# 1.net
KiCad netlist of a schematic drawn in Altium Designer
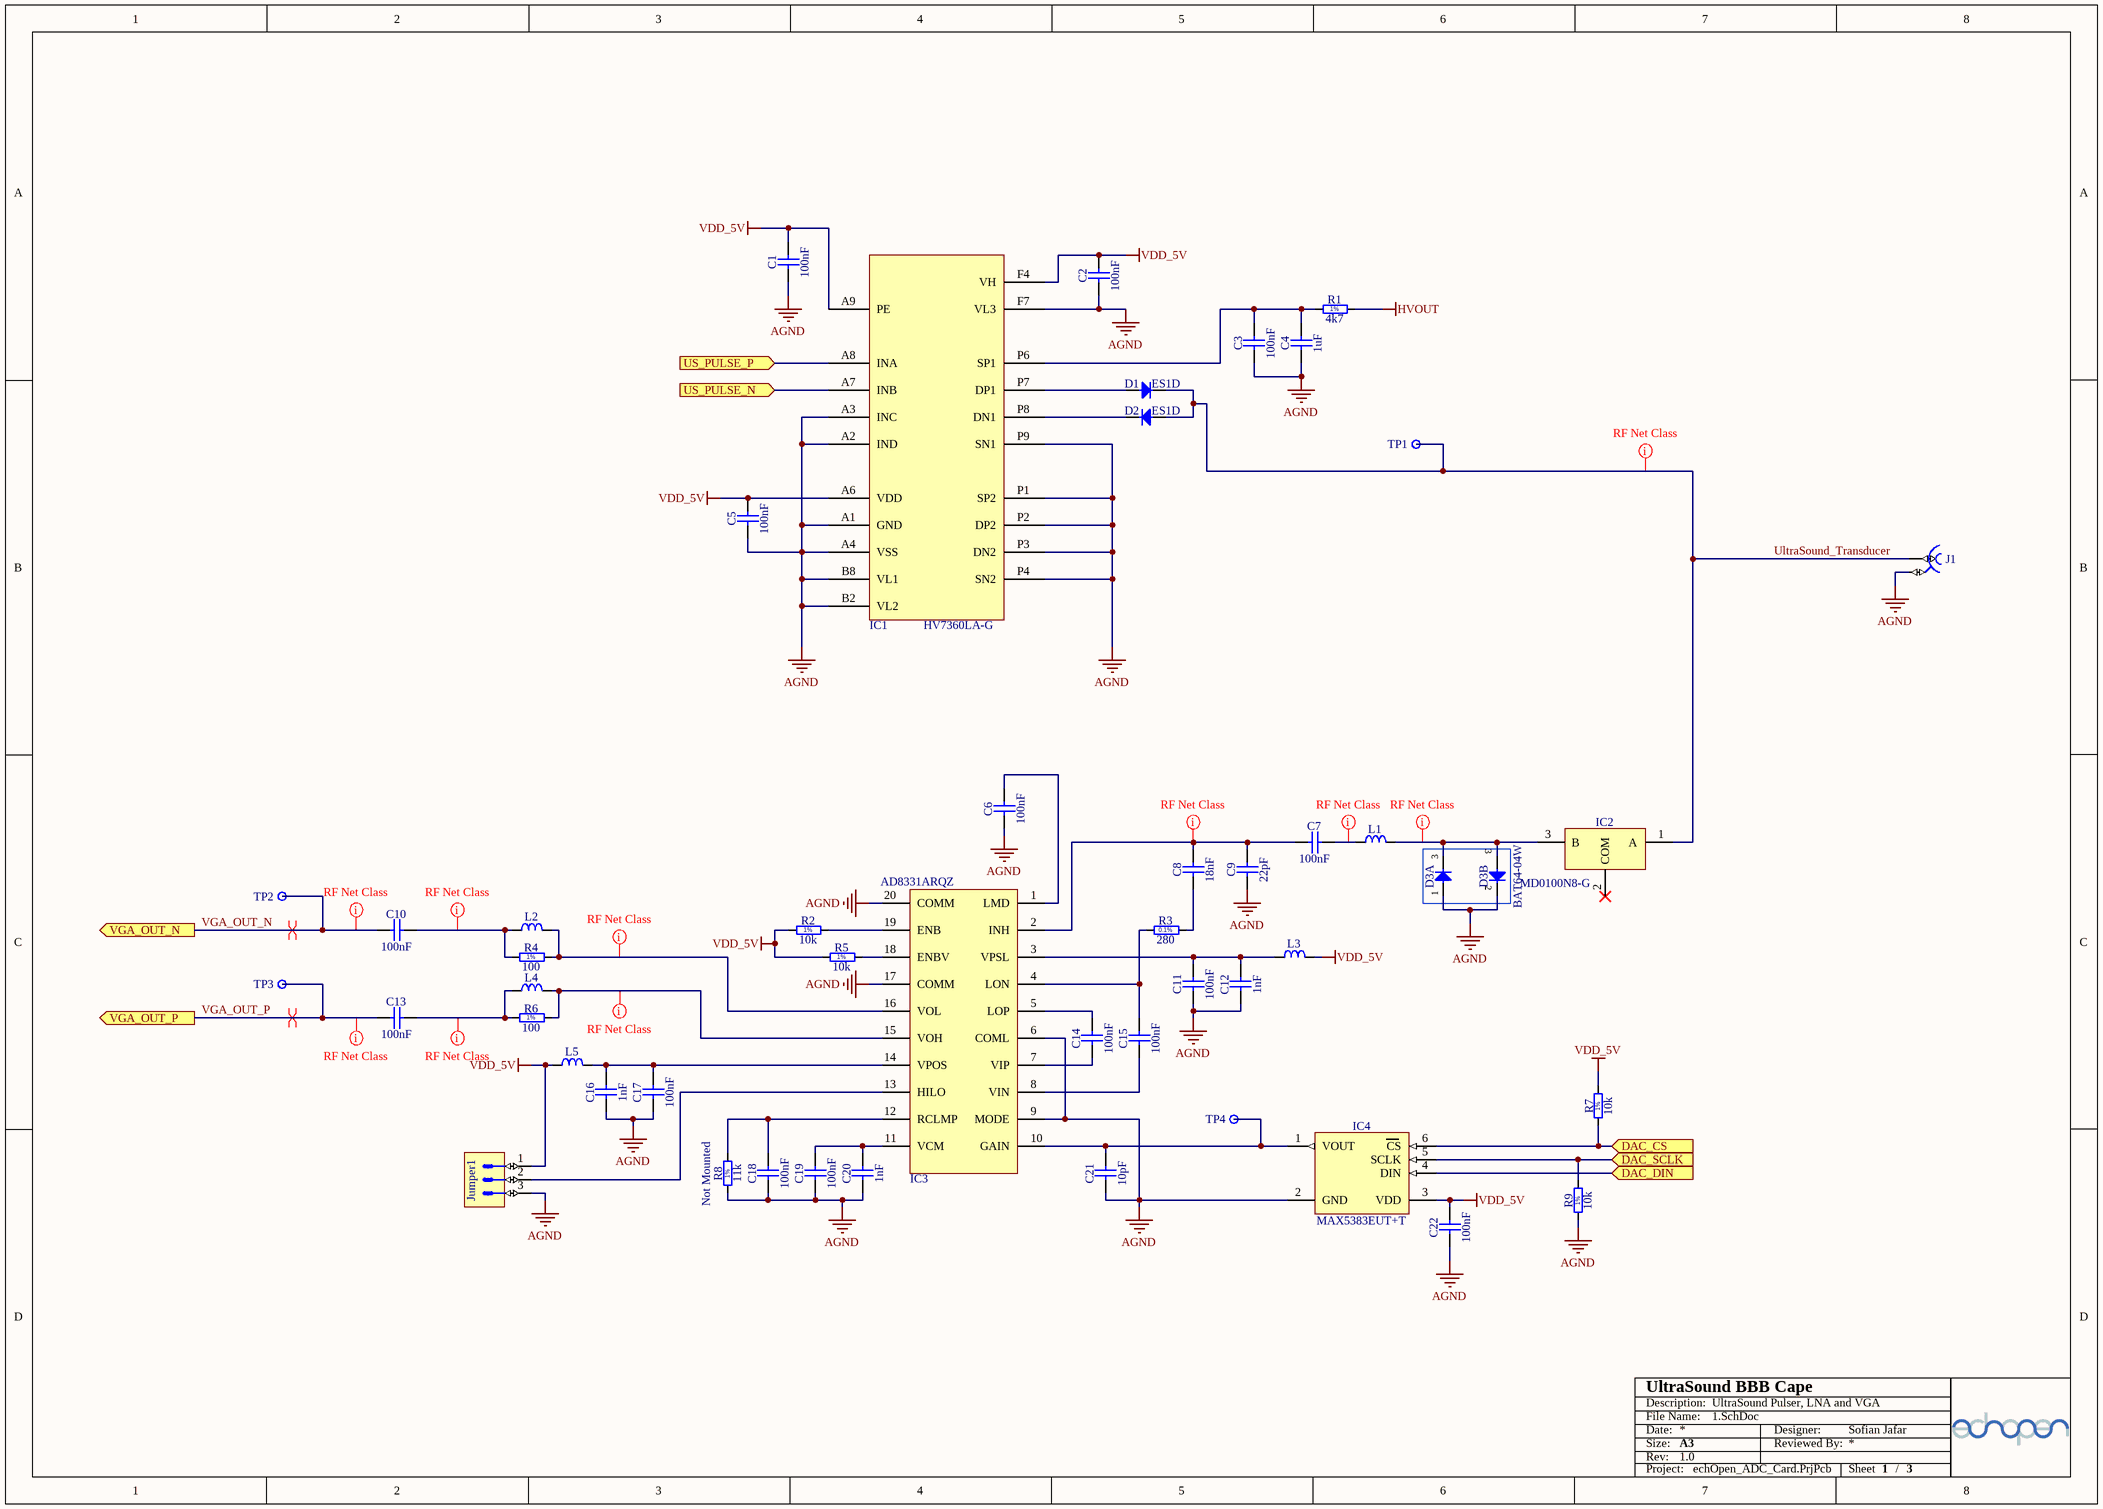
[diagram p0: 1.SchDoc]

(export (version "E")
  (design (tool "Eeschema 10.0.6"))
  (components
    (comp (ref "C1")
      (value "100nF")
      (footprint "CAPC1608X87N")
      (description "Non-polarised capacitor")
      (fields
        (field (name "PART NUMBER") "CC0603_100NF_50V_10%_X7R")
        (field (name "VOLTAGE") "50V")
        (field (name "AUTHOR") "CERN DEM JLC")
      )
      (libsource (lib "Sof-Capacitors") (part "Capacitor - non polarized"))
    )
    (comp (ref "C2")
      (value "100nF")
      (footprint "CAPC1608X87N")
      (description "Non-polarised capacitor")
      (fields
        (field (name "PART NUMBER") "CC0603_100NF_50V_10%_X7R")
        (field (name "VOLTAGE") "50V")
        (field (name "AUTHOR") "CERN DEM JLC")
      )
      (libsource (lib "Sof-Capacitors") (part "Capacitor - non polarized"))
    )
    (comp (ref "C3")
      (value "100nF")
      (footprint "CAPC1608X87N")
      (description "Non-polarised capacitor")
      (fields
        (field (name "PART NUMBER") "CC0603_100NF_50V_10%_X7R")
        (field (name "VOLTAGE") "50V")
        (field (name "AUTHOR") "CERN DEM JLC")
      )
      (libsource (lib "Sof-Capacitors") (part "Capacitor - non polarized"))
    )
    (comp (ref "C4")
      (value "1uF")
      (footprint "CAPC5650X165N")
      (description "Non-polarised capacitor")
      (fields
        (field (name "PART NUMBER") "CC2220_1UF_200V_10%_X7R")
        (field (name "VOLTAGE") "200V")
        (field (name "AUTHOR") "CERN DEM JLC")
      )
      (libsource (lib "Sof-Capacitors") (part "Capacitor - non polarized"))
    )
    (comp (ref "C5")
      (value "100nF")
      (footprint "CAPC1608X87N")
      (description "Non-polarised capacitor")
      (fields
        (field (name "PART NUMBER") "CC0603_100NF_50V_10%_X7R")
        (field (name "VOLTAGE") "50V")
        (field (name "AUTHOR") "CERN DEM JLC")
      )
      (libsource (lib "Sof-Capacitors") (part "Capacitor - non polarized"))
    )
    (comp (ref "C6")
      (value "100nF")
      (footprint "CAPC1608X87N")
      (description "Non-polarised capacitor")
      (fields
        (field (name "PART NUMBER") "CC0603_100NF_50V_10%_X7R")
        (field (name "VOLTAGE") "50V")
        (field (name "AUTHOR") "CERN DEM JLC")
      )
      (libsource (lib "Sof-Capacitors") (part "Capacitor - non polarized"))
    )
    (comp (ref "C7")
      (value "100nF")
      (footprint "CAPC1608X87N")
      (description "Non-polarised capacitor")
      (fields
        (field (name "PART NUMBER") "CC0603_100NF_50V_10%_X7R")
        (field (name "VOLTAGE") "50V")
        (field (name "AUTHOR") "CERN DEM JLC")
      )
      (libsource (lib "Sof-Capacitors") (part "Capacitor - non polarized"))
    )
    (comp (ref "C8")
      (value "18nF")
      (footprint "CAPC1608X87N")
      (description "Non-polarised capacitor")
      (fields
        (field (name "PART NUMBER") "CC0603_18NF_50V_10%_X7R")
        (field (name "VOLTAGE") "50V")
        (field (name "AUTHOR") "CERN DEM JLC")
      )
      (libsource (lib "Sof-Capacitors") (part "Capacitor - non polarized"))
    )
    (comp (ref "C9")
      (value "22pF")
      (footprint "CAPC1608X87N")
      (description "Non-polarised capacitor")
      (fields
        (field (name "PART NUMBER") "CC0603_22PF_50V_5%_NP0")
        (field (name "VOLTAGE") "50V")
        (field (name "AUTHOR") "CERN DEM JLC")
      )
      (libsource (lib "Sof-Capacitors") (part "Capacitor - non polarized"))
    )
    (comp (ref "C10")
      (value "100nF")
      (footprint "CAPC1608X87N")
      (description "Non-polarised capacitor")
      (fields
        (field (name "PART NUMBER") "CC0603_100NF_50V_10%_X7R")
        (field (name "VOLTAGE") "50V")
        (field (name "AUTHOR") "CERN DEM JLC")
      )
      (libsource (lib "Sof-Capacitors") (part "Capacitor - non polarized"))
    )
    (comp (ref "C11")
      (value "100nF")
      (footprint "CAPC1608X87N")
      (description "Non-polarised capacitor")
      (fields
        (field (name "PART NUMBER") "CC0603_100NF_50V_10%_X7R")
        (field (name "VOLTAGE") "50V")
        (field (name "AUTHOR") "CERN DEM JLC")
      )
      (libsource (lib "Sof-Capacitors") (part "Capacitor - non polarized"))
    )
    (comp (ref "C12")
      (value "1nF")
      (footprint "CAPC1608X87N")
      (description "Non-polarised capacitor")
      (fields
        (field (name "PART NUMBER") "CC0603_1NF_50V_10%_X7R")
        (field (name "VOLTAGE") "50V")
        (field (name "AUTHOR") "CERN DEM JLC")
      )
      (libsource (lib "Sof-Capacitors") (part "Capacitor - non polarized"))
    )
    (comp (ref "C13")
      (value "100nF")
      (footprint "CAPC1608X87N")
      (description "Non-polarised capacitor")
      (fields
        (field (name "PART NUMBER") "CC0603_100NF_50V_10%_X7R")
        (field (name "VOLTAGE") "50V")
        (field (name "AUTHOR") "CERN DEM JLC")
      )
      (libsource (lib "Sof-Capacitors") (part "Capacitor - non polarized"))
    )
    (comp (ref "C14")
      (value "100nF")
      (footprint "CAPC1608X87N")
      (description "Non-polarised capacitor")
      (fields
        (field (name "PART NUMBER") "CC0603_100NF_50V_10%_X7R")
        (field (name "VOLTAGE") "50V")
        (field (name "AUTHOR") "CERN DEM JLC")
      )
      (libsource (lib "Sof-Capacitors") (part "Capacitor - non polarized"))
    )
    (comp (ref "C15")
      (value "100nF")
      (footprint "CAPC1608X87N")
      (description "Non-polarised capacitor")
      (fields
        (field (name "PART NUMBER") "CC0603_100NF_50V_10%_X7R")
        (field (name "VOLTAGE") "50V")
        (field (name "AUTHOR") "CERN DEM JLC")
      )
      (libsource (lib "Sof-Capacitors") (part "Capacitor - non polarized"))
    )
    (comp (ref "C16")
      (value "1nF")
      (footprint "CAPC1608X87N")
      (description "Non-polarised capacitor")
      (fields
        (field (name "PART NUMBER") "CC0603_1NF_50V_10%_X7R")
        (field (name "VOLTAGE") "50V")
        (field (name "AUTHOR") "CERN DEM JLC")
      )
      (libsource (lib "Sof-Capacitors") (part "Capacitor - non polarized"))
    )
    (comp (ref "C17")
      (value "100nF")
      (footprint "CAPC1608X87N")
      (description "Non-polarised capacitor")
      (fields
        (field (name "PART NUMBER") "CC0603_100NF_50V_10%_X7R")
        (field (name "VOLTAGE") "50V")
        (field (name "AUTHOR") "CERN DEM JLC")
      )
      (libsource (lib "Sof-Capacitors") (part "Capacitor - non polarized"))
    )
    (comp (ref "C18")
      (value "100nF")
      (footprint "CAPC1608X87N")
      (description "Non-polarised capacitor")
      (fields
        (field (name "PART NUMBER") "CC0603_100NF_50V_10%_X7R")
        (field (name "VOLTAGE") "50V")
        (field (name "AUTHOR") "CERN DEM JLC")
      )
      (libsource (lib "Sof-Capacitors") (part "Capacitor - non polarized"))
    )
    (comp (ref "C19")
      (value "100nF")
      (footprint "CAPC1608X87N")
      (description "Non-polarised capacitor")
      (fields
        (field (name "PART NUMBER") "CC0603_100NF_50V_10%_X7R")
        (field (name "VOLTAGE") "50V")
        (field (name "AUTHOR") "CERN DEM JLC")
      )
      (libsource (lib "Sof-Capacitors") (part "Capacitor - non polarized"))
    )
    (comp (ref "C20")
      (value "1nF")
      (footprint "CAPC1608X87N")
      (description "Non-polarised capacitor")
      (fields
        (field (name "PART NUMBER") "CC0603_1NF_50V_10%_X7R")
        (field (name "VOLTAGE") "50V")
        (field (name "AUTHOR") "CERN DEM JLC")
      )
      (libsource (lib "Sof-Capacitors") (part "Capacitor - non polarized"))
    )
    (comp (ref "C21")
      (value "10pF")
      (footprint "CAPC1608X87N")
      (description "Non-polarised capacitor")
      (fields
        (field (name "PART NUMBER") "CC0603_10PF_50V_5%_NP0")
        (field (name "VOLTAGE") "50V")
        (field (name "AUTHOR") "CERN DEM JLC")
      )
      (libsource (lib "Sof-Capacitors") (part "Capacitor - non polarized"))
    )
    (comp (ref "C22")
      (value "100nF")
      (footprint "CAPC1608X87N")
      (description "Non-polarised capacitor")
      (fields
        (field (name "PART NUMBER") "CC0603_100NF_50V_10%_X7R")
        (field (name "VOLTAGE") "50V")
        (field (name "AUTHOR") "CERN DEM JLC")
      )
      (libsource (lib "Sof-Capacitors") (part "Capacitor - non polarized"))
    )
    (comp (ref "D1")
      (value "ES1D")
      (footprint "DIOM5027X244N")
      (description "Diode")
      (fields
        (field (name "VOLTAGE") "200V")
        (field (name "POWER") "1A")
        (field (name "AUTHOR") "CERN DEM JLC")
      )
      (libsource (lib "Sof-ICs And Semiconductors") (part "Diode"))
    )
    (comp (ref "D2")
      (value "ES1D")
      (footprint "DIOM5027X244N")
      (description "Diode")
      (fields
        (field (name "VOLTAGE") "200V")
        (field (name "POWER") "1A")
        (field (name "AUTHOR") "CERN DEM JLC")
      )
      (libsource (lib "Sof-ICs And Semiconductors") (part "Diode"))
    )
    (comp (ref "D3")
      (value "BAT64-04W")
      (footprint "SOT65P210X100-3N")
      (description "Serial Diode")
      (fields
        (field (name "VOLTAGE") "40V")
        (field (name "POWER") "250mW")
        (field (name "AUTHOR") "CERN DEM JMW")
      )
      (libsource (lib "Sof-ICs And Semiconductors") (part "Diode x2 A1C3_A3C2"))
    )
    (comp (ref "IC1")
      (value "HV7360LA-G")
      (footprint "HV7360")
      (fields (field (name "MANUFACTURER") "Supertex inc.") (field (name "AUTHOR") "S. Jafar"))
      (libsource (lib "Sof-ICs And Semiconductors") (part "HV7360"))
    )
    (comp (ref "IC2")
      (value "MD0100N8-G")
      (footprint "SOT89")
      (description "3-Ultra-Sound HV Switch 1=A 2=COM 3=B")
      (fields (field (name "MANUFACTURER") "Supertex inc.") (field (name "AUTHOR") "S. Jafar"))
      (libsource (lib "Sof-ICs And Semiconductors") (part "MD0100"))
    )
    (comp (ref "IC3")
      (value "AD8331ARQZ")
      (footprint "SOP64P600X175-20N")
      (fields (field (name "MANUFACTURER") "Analog Devices") (field (name "AUTHOR") "S. Jafar"))
      (libsource (lib "Sof-ICs And Semiconductors") (part "AD8331"))
    )
    (comp (ref "IC4")
      (value "MAX5383EUT+T")
      (footprint "SOT95P280X100-6N")
      (description "Low-Cost, Low-Power, 8-Bit DACs with 3-Wire  Serial Interface in SOT23")
      (fields (field (name "MANUFACTURER") "MAXIM") (field (name "AUTHOR") "S. Jafar"))
      (libsource (lib "Sof-ICs And Semiconductors") (part "MAX5383"))
    )
    (comp (ref "J1")
      (value "SMA")
      (footprint "AMPHENOL_132357-11")
      (fields
        (field (name "PART NUMBER") "AMPHENOL_132357-11")
        (field (name "MANUFACTURER") "AMPHENOL")
        (field (name "MANUFACTURER PART NUMBER") "132357-11")
        (field (name "AUTHOR") "CERN DEM JLC")
      )
      (libsource (lib "Sof-Connectors") (part "Coax_1Female_1Shield"))
    )
    (comp (ref "Jumper1")
      (value "~")
      (footprint "SULLINS_GRPB031VWVN")
      (description "Connector 3 Male")
      (fields
        (field (name "PART NUMBER") "SULLINS_GRPB031VWVN")
        (field (name "MANUFACTURER") "SULLINS")
        (field (name "AUTHOR") "S. Jafar")
      )
      (libsource (lib "Sof-Connectors") (part "Connector 3 Male"))
    )
    (comp (ref "L1")
      (value "75R@100MHz")
      (footprint "INDC2012X105N")
      (description "Inductor")
      (fields
        (field (name "PART NUMBER") "IND0805_MURATA_BLM21BB750SN1D")
        (field (name "POWER") "700mA")
        (field (name "AUTHOR") "S. Jafar")
      )
      (libsource (lib "Sof-Inductors & Transformers") (part "Inductor"))
    )
    (comp (ref "L2")
      (value "75R@100MHz")
      (footprint "INDC2012X105N")
      (description "Inductor")
      (fields
        (field (name "PART NUMBER") "IND0805_MURATA_BLM21BB750SN1D")
        (field (name "POWER") "700mA")
        (field (name "AUTHOR") "S. Jafar")
      )
      (libsource (lib "Sof-Inductors & Transformers") (part "Inductor"))
    )
    (comp (ref "L3")
      (value "75R@100MHz")
      (footprint "INDC2012X105N")
      (description "Inductor")
      (fields
        (field (name "PART NUMBER") "IND0805_MURATA_BLM21BB750SN1D")
        (field (name "POWER") "700mA")
        (field (name "AUTHOR") "S. Jafar")
      )
      (libsource (lib "Sof-Inductors & Transformers") (part "Inductor"))
    )
    (comp (ref "L4")
      (value "75R@100MHz")
      (footprint "INDC2012X105N")
      (description "Inductor")
      (fields
        (field (name "PART NUMBER") "IND0805_MURATA_BLM21BB750SN1D")
        (field (name "POWER") "700mA")
        (field (name "AUTHOR") "S. Jafar")
      )
      (libsource (lib "Sof-Inductors & Transformers") (part "Inductor"))
    )
    (comp (ref "L5")
      (value "75R@100MHz")
      (footprint "INDC2012X105N")
      (description "Inductor")
      (fields
        (field (name "PART NUMBER") "IND0805_MURATA_BLM21BB750SN1D")
        (field (name "POWER") "700mA")
        (field (name "AUTHOR") "S. Jafar")
      )
      (libsource (lib "Sof-Inductors & Transformers") (part "Inductor"))
    )
    (comp (ref "R1")
      (value "4k7")
      (footprint "RESC3216X65N")
      (description "Resistor - 1%")
      (fields
        (field (name "PART NUMBER") "R1206_4K7_1%_0.25W_100PPM")
        (field (name "POWER") "0.25W")
        (field (name "AUTHOR") "CERN DEM JLC")
      )
      (libsource (lib "Sof-Resistors") (part "Resistor - 1%"))
    )
    (comp (ref "R2")
      (value "10k")
      (footprint "RESC1608X55N")
      (description "Resistor - 1%")
      (fields
        (field (name "PART NUMBER") "R0603_10K_1%_0.1W_100PPM")
        (field (name "POWER") "0.1W")
        (field (name "AUTHOR") "CERN DEM JLC")
      )
      (libsource (lib "Sof-Resistors") (part "Resistor - 1%"))
    )
    (comp (ref "R3")
      (value "280")
      (footprint "RESC1608X55N")
      (description "Resistor - 0.1%")
      (fields
        (field (name "PART NUMBER") "R0603_280R_0.1%_0.063W_10PPM")
        (field (name "POWER") "0.063W")
        (field (name "AUTHOR") "CERN DEM JLC")
      )
      (libsource (lib "Sof-Resistors") (part "Resistor - 0.1%"))
    )
    (comp (ref "R4")
      (value "100")
      (footprint "RESC1608X55N")
      (description "Resistor - 1%")
      (fields
        (field (name "PART NUMBER") "R0603_100R_1%_0.1W_100PPM")
        (field (name "POWER") "0.1W")
        (field (name "AUTHOR") "CERN DEM JLC")
      )
      (libsource (lib "Sof-Resistors") (part "Resistor - 1%"))
    )
    (comp (ref "R5")
      (value "10k")
      (footprint "RESC1608X55N")
      (description "Resistor - 1%")
      (fields
        (field (name "PART NUMBER") "R0603_10K_1%_0.1W_100PPM")
        (field (name "POWER") "0.1W")
        (field (name "AUTHOR") "CERN DEM JLC")
      )
      (libsource (lib "Sof-Resistors") (part "Resistor - 1%"))
    )
    (comp (ref "R6")
      (value "100")
      (footprint "RESC1608X55N")
      (description "Resistor - 1%")
      (fields
        (field (name "PART NUMBER") "R0603_100R_1%_0.1W_100PPM")
        (field (name "POWER") "0.1W")
        (field (name "AUTHOR") "CERN DEM JLC")
      )
      (libsource (lib "Sof-Resistors") (part "Resistor - 1%"))
    )
    (comp (ref "R7")
      (value "10k")
      (footprint "RESC1608X55N")
      (description "Resistor - 1%")
      (fields
        (field (name "PART NUMBER") "R0603_10K_1%_0.1W_100PPM")
        (field (name "POWER") "0.1W")
        (field (name "AUTHOR") "CERN DEM JLC")
      )
      (libsource (lib "Sof-Resistors") (part "Resistor - 1%"))
    )
    (comp (ref "R8")
      (value "11k")
      (footprint "RESC1005X40N")
      (description "Resistor - 1%")
      (fields
        (field (name "PART NUMBER") "R0402_11K_1%_0.0625W_100PPM")
        (field (name "POWER") "0.0625W")
        (field (name "MOUNTED") "Not Mounted")
        (field (name "AUTHOR") "CERN DEM JLC")
      )
      (libsource (lib "Sof-Resistors") (part "Resistor - 1%"))
    )
    (comp (ref "R9")
      (value "10k")
      (footprint "RESC1608X55N")
      (description "Resistor - 1%")
      (fields
        (field (name "PART NUMBER") "R0603_10K_1%_0.1W_100PPM")
        (field (name "POWER") "0.1W")
        (field (name "AUTHOR") "CERN DEM JLC")
      )
      (libsource (lib "Sof-Resistors") (part "Resistor - 1%"))
    )
    (comp (ref "TP1")
      (value "Test Point")
      (footprint "NICOMATIC_C12000B")
      (fields
        (field (name "PART NUMBER") "NICOMATIC_C12000B")
        (field (name "MANUFACTURER") "NICOMATIC")
        (field (name "MANUFACTURER PART NUMBER") "C12000B")
        (field (name "AUTHOR") "CERN DEM JLC")
      )
      (libsource (lib "Sof-Connectors") (part "Test Point"))
    )
    (comp (ref "TP2")
      (value "Test Point")
      (footprint "NICOMATIC_C12000B")
      (fields
        (field (name "PART NUMBER") "NICOMATIC_C12000B")
        (field (name "MANUFACTURER") "NICOMATIC")
        (field (name "MANUFACTURER PART NUMBER") "C12000B")
        (field (name "AUTHOR") "CERN DEM JLC")
      )
      (libsource (lib "Sof-Connectors") (part "Test Point"))
    )
    (comp (ref "TP3")
      (value "Test Point")
      (footprint "NICOMATIC_C12000B")
      (fields
        (field (name "PART NUMBER") "NICOMATIC_C12000B")
        (field (name "MANUFACTURER") "NICOMATIC")
        (field (name "MANUFACTURER PART NUMBER") "C12000B")
        (field (name "AUTHOR") "CERN DEM JLC")
      )
      (libsource (lib "Sof-Connectors") (part "Test Point"))
    )
    (comp (ref "TP4")
      (value "Test Point")
      (footprint "NICOMATIC_C12000B")
      (fields
        (field (name "PART NUMBER") "NICOMATIC_C12000B")
        (field (name "MANUFACTURER") "NICOMATIC")
        (field (name "MANUFACTURER PART NUMBER") "C12000B")
        (field (name "AUTHOR") "CERN DEM JLC")
      )
      (libsource (lib "Sof-Connectors") (part "Test Point"))
    )
  )
  (nets
    (net (code "1") (name "/DAC_CS") (class "Default")
      (node (ref "IC4") (pin "6") (pinfunction "CS_6") (pintype "input"))
      (node (ref "R7") (pin "1") (pinfunction "1_1") (pintype "passive"))
    )
    (net (code "2") (name "/DAC_DIN") (class "Default")
      (node (ref "IC4") (pin "4") (pinfunction "DIN_4") (pintype "input"))
    )
    (net (code "3") (name "/DAC_SCLK") (class "Default")
      (node (ref "IC4") (pin "5") (pinfunction "SCLK_5") (pintype "input"))
      (node (ref "R9") (pin "2") (pinfunction "2_2") (pintype "passive"))
    )
    (net (code "4") (name "/US_PULSE_N") (class "Default")
      (node (ref "IC1") (pin "A7") (pinfunction "INB_A7") (pintype "passive"))
    )
    (net (code "5") (name "/US_PULSE_P") (class "Default")
      (node (ref "IC1") (pin "A8") (pinfunction "INA_A8") (pintype "passive"))
    )
    (net (code "6") (name "/UltraSound_Transducer") (class "Default")
      (node (ref "D1") (pin "1") (pinfunction "C_1") (pintype "passive"))
      (node (ref "D2") (pin "2") (pinfunction "A_2") (pintype "passive"))
      (node (ref "IC2") (pin "1") (pinfunction "A_1") (pintype "passive"))
      (node (ref "J1") (pin "1") (pinfunction "1_1") (pintype "bidirectional"))
      (node (ref "TP1") (pin "1") (pinfunction "1_1") (pintype "bidirectional"))
    )
    (net (code "7") (name "/VGA_OUT_N") (class "Default")
      (node (ref "C10") (pin "2") (pinfunction "2_2") (pintype "passive"))
      (node (ref "TP2") (pin "1") (pinfunction "1_1") (pintype "bidirectional"))
    )
    (net (code "8") (name "/VGA_OUT_P") (class "Default")
      (node (ref "C13") (pin "2") (pinfunction "2_2") (pintype "passive"))
      (node (ref "TP3") (pin "1") (pinfunction "1_1") (pintype "bidirectional"))
    )
    (net (code "9") (name "AGND") (class "Default")
      (node (ref "C1") (pin "1") (pinfunction "1_1") (pintype "passive"))
      (node (ref "C11") (pin "1") (pinfunction "1_1") (pintype "passive"))
      (node (ref "C12") (pin "1") (pinfunction "1_1") (pintype "passive"))
      (node (ref "C16") (pin "1") (pinfunction "1_1") (pintype "passive"))
      (node (ref "C17") (pin "2") (pinfunction "2_2") (pintype "passive"))
      (node (ref "C18") (pin "2") (pinfunction "2_2") (pintype "passive"))
      (node (ref "C19") (pin "2") (pinfunction "2_2") (pintype "passive"))
      (node (ref "C2") (pin "1") (pinfunction "1_1") (pintype "passive"))
      (node (ref "C20") (pin "1") (pinfunction "1_1") (pintype "passive"))
      (node (ref "C21") (pin "1") (pinfunction "1_1") (pintype "passive"))
      (node (ref "C22") (pin "1") (pinfunction "1_1") (pintype "passive"))
      (node (ref "C3") (pin "1") (pinfunction "1_1") (pintype "passive"))
      (node (ref "C4") (pin "1") (pinfunction "1_1") (pintype "passive"))
      (node (ref "C5") (pin "1") (pinfunction "1_1") (pintype "passive"))
      (node (ref "C6") (pin "2") (pinfunction "2_2") (pintype "passive"))
      (node (ref "C9") (pin "1") (pinfunction "1_1") (pintype "passive"))
      (node (ref "D3") (pin "1") (pinfunction "A_1") (pintype "passive"))
      (node (ref "D3") (pin "2") (pinfunction "C_2") (pintype "passive"))
      (node (ref "IC1") (pin "A1") (pinfunction "GND_A1") (pintype "passive"))
      (node (ref "IC1") (pin "A2") (pinfunction "IND_A2") (pintype "passive"))
      (node (ref "IC1") (pin "A3") (pinfunction "INC_A3") (pintype "passive"))
      (node (ref "IC1") (pin "A4") (pinfunction "VSS_A4") (pintype "passive"))
      (node (ref "IC1") (pin "B2") (pinfunction "VL2_B2") (pintype "passive"))
      (node (ref "IC1") (pin "B8") (pinfunction "VL1_B8") (pintype "passive"))
      (node (ref "IC1") (pin "F7") (pinfunction "VL3_F7") (pintype "passive"))
      (node (ref "IC1") (pin "P1") (pinfunction "SP2_P1") (pintype "passive"))
      (node (ref "IC1") (pin "P2") (pinfunction "DP2_P2") (pintype "passive"))
      (node (ref "IC1") (pin "P3") (pinfunction "DN2_P3") (pintype "passive"))
      (node (ref "IC1") (pin "P4") (pinfunction "SN2_P4") (pintype "passive"))
      (node (ref "IC1") (pin "P9") (pinfunction "SN1_P9") (pintype "passive"))
      (node (ref "IC3") (pin "17") (pinfunction "COMM_17") (pintype "passive"))
      (node (ref "IC3") (pin "20") (pinfunction "COMM_20") (pintype "passive"))
      (node (ref "IC3") (pin "6") (pinfunction "COML_6") (pintype "passive"))
      (node (ref "IC3") (pin "9") (pinfunction "MODE_9") (pintype "passive"))
      (node (ref "IC4") (pin "2") (pinfunction "GND_2") (pintype "power_in"))
      (node (ref "J1") (pin "2") (pinfunction "2_2") (pintype "bidirectional"))
      (node (ref "Jumper1") (pin "3") (pinfunction "3_3") (pintype "bidirectional"))
      (node (ref "R8") (pin "1") (pinfunction "1_1") (pintype "passive"))
      (node (ref "R9") (pin "1") (pinfunction "1_1") (pintype "passive"))
    )
    (net (code "10") (name "HVOUT") (class "Default")
      (node (ref "R1") (pin "2") (pinfunction "2_2") (pintype "passive"))
    )
    (net (code "11") (name "Net-(C7-Pad1)") (class "Default")
      (node (ref "C7") (pin "1") (pinfunction "1_1") (pintype "passive"))
      (node (ref "L1") (pin "1") (pinfunction "1_1") (pintype "passive"))
    )
    (net (code "12") (name "Net-(C8-Pad1)") (class "Default")
      (node (ref "C8") (pin "1") (pinfunction "1_1") (pintype "passive"))
      (node (ref "R3") (pin "2") (pinfunction "2_2") (pintype "passive"))
    )
    (net (code "13") (name "Net-(C10-Pad1)") (class "Default")
      (node (ref "C10") (pin "1") (pinfunction "1_1") (pintype "passive"))
      (node (ref "L2") (pin "1") (pinfunction "1_1") (pintype "passive"))
      (node (ref "R4") (pin "1") (pinfunction "1_1") (pintype "passive"))
    )
    (net (code "14") (name "Net-(C13-Pad1)") (class "Default")
      (node (ref "C13") (pin "1") (pinfunction "1_1") (pintype "passive"))
      (node (ref "L4") (pin "1") (pinfunction "1_1") (pintype "passive"))
      (node (ref "R6") (pin "1") (pinfunction "1_1") (pintype "passive"))
    )
    (net (code "15") (name "Net-(D1-A)") (class "Default")
      (node (ref "D1") (pin "2") (pinfunction "A_2") (pintype "passive"))
      (node (ref "IC1") (pin "P7") (pinfunction "DP1_P7") (pintype "passive"))
    )
    (net (code "16") (name "Net-(D2-C)") (class "Default")
      (node (ref "D2") (pin "1") (pinfunction "C_1") (pintype "passive"))
      (node (ref "IC1") (pin "P8") (pinfunction "DN1_P8") (pintype "passive"))
    )
    (net (code "17") (name "Net-(D3A-COMAC)") (class "Default")
      (node (ref "D3") (pin "3") (pinfunction "COMAC_3") (pintype "passive"))
      (node (ref "IC2") (pin "3") (pinfunction "B_3") (pintype "passive"))
      (node (ref "L1") (pin "2") (pinfunction "2_2") (pintype "passive"))
    )
    (net (code "18") (name "Net-(IC1-SP1)") (class "Default")
      (node (ref "C3") (pin "2") (pinfunction "2_2") (pintype "passive"))
      (node (ref "C4") (pin "2") (pinfunction "2_2") (pintype "passive"))
      (node (ref "IC1") (pin "P6") (pinfunction "SP1_P6") (pintype "passive"))
      (node (ref "R1") (pin "1") (pinfunction "1_1") (pintype "passive"))
    )
    (net (code "19") (name "Net-(IC3-ENB)") (class "Default")
      (node (ref "IC3") (pin "19") (pinfunction "ENB_19") (pintype "passive"))
      (node (ref "R2") (pin "2") (pinfunction "2_2") (pintype "passive"))
    )
    (net (code "20") (name "Net-(IC3-ENBV)") (class "Default")
      (node (ref "IC3") (pin "18") (pinfunction "ENBV_18") (pintype "passive"))
      (node (ref "R5") (pin "2") (pinfunction "2_2") (pintype "passive"))
    )
    (net (code "21") (name "Net-(IC3-GAIN)") (class "Default")
      (node (ref "C21") (pin "2") (pinfunction "2_2") (pintype "passive"))
      (node (ref "IC3") (pin "10") (pinfunction "GAIN_10") (pintype "passive"))
      (node (ref "IC4") (pin "1") (pinfunction "VOUT_1") (pintype "output"))
      (node (ref "TP4") (pin "1") (pinfunction "1_1") (pintype "bidirectional"))
    )
    (net (code "22") (name "Net-(IC3-HILO)") (class "Default")
      (node (ref "IC3") (pin "13") (pinfunction "HILO_13") (pintype "passive"))
      (node (ref "Jumper1") (pin "2") (pinfunction "2_2") (pintype "bidirectional"))
    )
    (net (code "23") (name "Net-(IC3-INH)") (class "Default")
      (node (ref "C7") (pin "2") (pinfunction "2_2") (pintype "passive"))
      (node (ref "C8") (pin "2") (pinfunction "2_2") (pintype "passive"))
      (node (ref "C9") (pin "2") (pinfunction "2_2") (pintype "passive"))
      (node (ref "IC3") (pin "2") (pinfunction "INH_2") (pintype "passive"))
    )
    (net (code "24") (name "Net-(IC3-LMD)") (class "Default")
      (node (ref "C6") (pin "1") (pinfunction "1_1") (pintype "passive"))
      (node (ref "IC3") (pin "1") (pinfunction "LMD_1") (pintype "passive"))
    )
    (net (code "25") (name "Net-(IC3-LON)") (class "Default")
      (node (ref "C15") (pin "1") (pinfunction "1_1") (pintype "passive"))
      (node (ref "IC3") (pin "4") (pinfunction "LON_4") (pintype "passive"))
      (node (ref "R3") (pin "1") (pinfunction "1_1") (pintype "passive"))
    )
    (net (code "26") (name "Net-(IC3-LOP)") (class "Default")
      (node (ref "C14") (pin "1") (pinfunction "1_1") (pintype "passive"))
      (node (ref "IC3") (pin "5") (pinfunction "LOP_5") (pintype "passive"))
    )
    (net (code "27") (name "Net-(IC3-RCLMP)") (class "Default")
      (node (ref "C18") (pin "1") (pinfunction "1_1") (pintype "passive"))
      (node (ref "IC3") (pin "12") (pinfunction "RCLMP_12") (pintype "passive"))
      (node (ref "R8") (pin "2") (pinfunction "2_2") (pintype "passive"))
    )
    (net (code "28") (name "Net-(IC3-VCM)") (class "Default")
      (node (ref "C19") (pin "1") (pinfunction "1_1") (pintype "passive"))
      (node (ref "C20") (pin "2") (pinfunction "2_2") (pintype "passive"))
      (node (ref "IC3") (pin "11") (pinfunction "VCM_11") (pintype "passive"))
    )
    (net (code "29") (name "Net-(IC3-VIN)") (class "Default")
      (node (ref "C15") (pin "2") (pinfunction "2_2") (pintype "passive"))
      (node (ref "IC3") (pin "8") (pinfunction "VIN_8") (pintype "passive"))
    )
    (net (code "30") (name "Net-(IC3-VIP)") (class "Default")
      (node (ref "C14") (pin "2") (pinfunction "2_2") (pintype "passive"))
      (node (ref "IC3") (pin "7") (pinfunction "VIP_7") (pintype "passive"))
    )
    (net (code "31") (name "Net-(IC3-VOH)") (class "Default")
      (node (ref "IC3") (pin "15") (pinfunction "VOH_15") (pintype "passive"))
      (node (ref "L4") (pin "2") (pinfunction "2_2") (pintype "passive"))
      (node (ref "R6") (pin "2") (pinfunction "2_2") (pintype "passive"))
    )
    (net (code "32") (name "Net-(IC3-VOL)") (class "Default")
      (node (ref "IC3") (pin "16") (pinfunction "VOL_16") (pintype "passive"))
      (node (ref "L2") (pin "2") (pinfunction "2_2") (pintype "passive"))
      (node (ref "R4") (pin "2") (pinfunction "2_2") (pintype "passive"))
    )
    (net (code "33") (name "Net-(IC3-VPOS)") (class "Default")
      (node (ref "C16") (pin "2") (pinfunction "2_2") (pintype "passive"))
      (node (ref "C17") (pin "1") (pinfunction "1_1") (pintype "passive"))
      (node (ref "IC3") (pin "14") (pinfunction "VPOS_14") (pintype "passive"))
      (node (ref "L5") (pin "2") (pinfunction "2_2") (pintype "passive"))
    )
    (net (code "34") (name "Net-(IC3-VPSL)") (class "Default")
      (node (ref "C11") (pin "2") (pinfunction "2_2") (pintype "passive"))
      (node (ref "C12") (pin "2") (pinfunction "2_2") (pintype "passive"))
      (node (ref "IC3") (pin "3") (pinfunction "VPSL_3") (pintype "passive"))
      (node (ref "L3") (pin "1") (pinfunction "1_1") (pintype "passive"))
    )
    (net (code "35") (name "VDD_5V") (class "Default")
      (node (ref "C1") (pin "2") (pinfunction "2_2") (pintype "passive"))
      (node (ref "C2") (pin "2") (pinfunction "2_2") (pintype "passive"))
      (node (ref "C22") (pin "2") (pinfunction "2_2") (pintype "passive"))
      (node (ref "C5") (pin "2") (pinfunction "2_2") (pintype "passive"))
      (node (ref "IC1") (pin "A6") (pinfunction "VDD_A6") (pintype "passive"))
      (node (ref "IC1") (pin "A9") (pinfunction "PE_A9") (pintype "passive"))
      (node (ref "IC1") (pin "F4") (pinfunction "VH_F4") (pintype "passive"))
      (node (ref "IC4") (pin "3") (pinfunction "VDD_3") (pintype "power_in"))
      (node (ref "Jumper1") (pin "1") (pinfunction "1_1") (pintype "bidirectional"))
      (node (ref "L3") (pin "2") (pinfunction "2_2") (pintype "passive"))
      (node (ref "L5") (pin "1") (pinfunction "1_1") (pintype "passive"))
      (node (ref "R2") (pin "1") (pinfunction "1_1") (pintype "passive"))
      (node (ref "R5") (pin "1") (pinfunction "1_1") (pintype "passive"))
      (node (ref "R7") (pin "2") (pinfunction "2_2") (pintype "passive"))
    )
    (net (code "36") (name "unconnected-(IC2-COM-Pad2)") (class "Default")
      (node (ref "IC2") (pin "2") (pinfunction "COM_2") (pintype "passive+no_connect"))
    )
  )
)
